# AAA_source-all_on_top.net
KiCad netlist of a schematic drawn in EAGLE
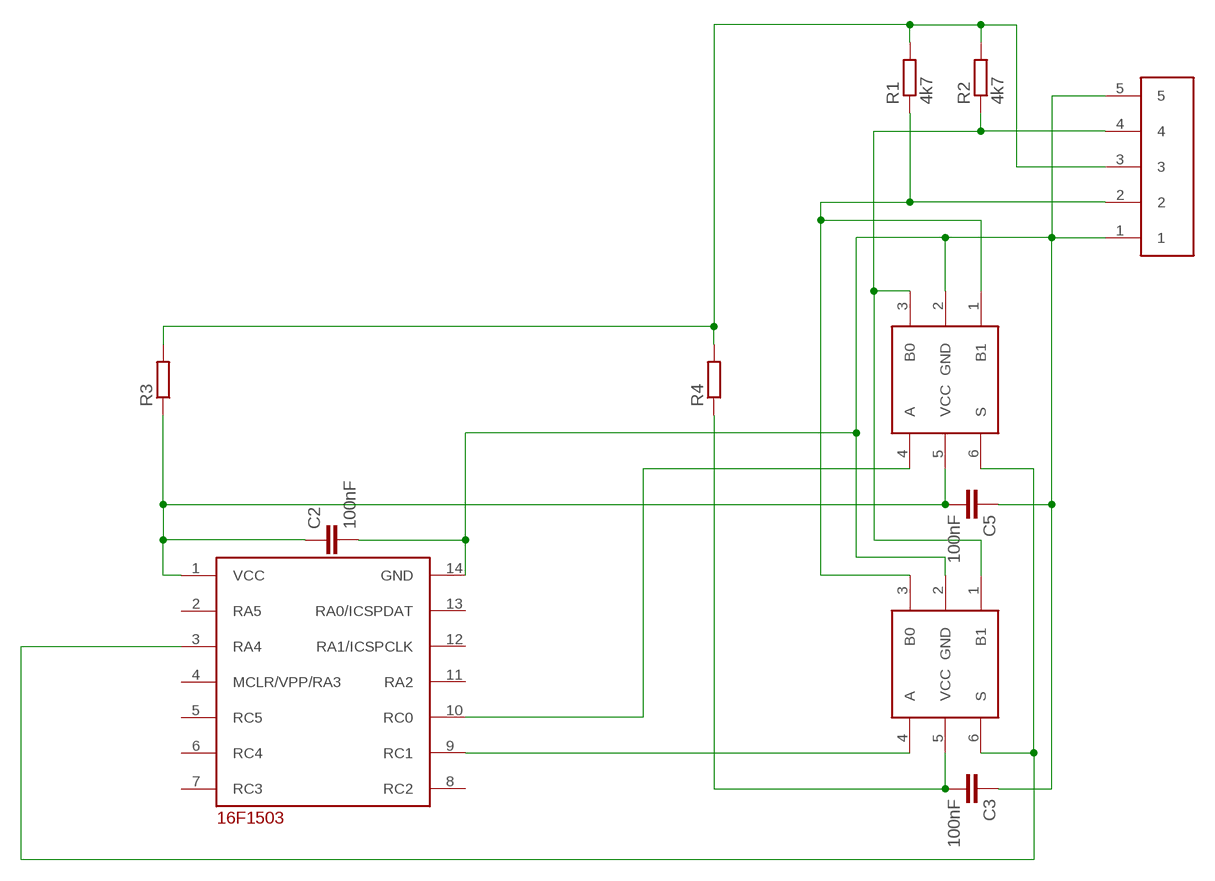
[diagram p0: schematic, sheet 1]

(export (version "E")
  (design (tool "Eeschema 10.0.6"))
  (components
    (comp (ref "C2")
      (value "100nF")
      (footprint "eagle-import:C0603")
      (libsource (lib "eagle-import") (part "C-EUC0603"))
    )
    (comp (ref "C3")
      (value "100nF")
      (footprint "eagle-import:C0603")
      (libsource (lib "eagle-import") (part "C-EUC0603"))
    )
    (comp (ref "C5")
      (value "100nF")
      (footprint "eagle-import:C0603")
      (libsource (lib "eagle-import") (part "C-EUC0603"))
    )
    (comp (ref "R1")
      (value "4k7")
      (footprint "eagle-import:R0603")
      (libsource (lib "eagle-import") (part "R-EU_R0603"))
    )
    (comp (ref "R2")
      (value "4k7")
      (footprint "eagle-import:R0603")
      (libsource (lib "eagle-import") (part "R-EU_R0603"))
    )
    (comp (ref "R3")
      (value "R-EU_R1206")
      (footprint "eagle-import:R1206")
      (libsource (lib "eagle-import") (part "R-EU_R1206"))
    )
    (comp (ref "R4")
      (value "R-EU_R1206")
      (footprint "eagle-import:R1206")
      (libsource (lib "eagle-import") (part "R-EU_R1206"))
    )
    (comp (ref "U$1")
      (value "16F103-TSSOP")
      (footprint "eagle-import:TSSOP14")
      (libsource (lib "eagle-import") (part "16F103-TSSOP"))
    )
    (comp (ref "U$5")
      (value "JUMPER5F-90")
      (footprint "eagle-import:JUMPER5F-90")
      (libsource (lib "eagle-import") (part "JUMPER5F-90"))
    )
    (comp (ref "U$6")
      (value "NC7SB3157P6X")
      (footprint "eagle-import:SC70-6L")
      (libsource (lib "eagle-import") (part "NC7SB3157P6X"))
    )
    (comp (ref "U$7")
      (value "NC7SB3157P6X")
      (footprint "eagle-import:SC70-6L")
      (libsource (lib "eagle-import") (part "NC7SB3157P6X"))
    )
  )
  (nets
    (net (code "1") (name "Net-(R1-Pad2)") (class "Default")
      (node (ref "R1") (pin "2") (pinfunction "2_2") (pintype "passive"))
      (node (ref "R2") (pin "2") (pinfunction "2_2") (pintype "passive"))
      (node (ref "R3") (pin "2") (pinfunction "2_2") (pintype "passive"))
      (node (ref "R4") (pin "2") (pinfunction "2_2") (pintype "passive"))
      (node (ref "U$5") (pin "3") (pinfunction "3_3") (pintype "bidirectional"))
    )
    (net (code "2") (name "Net-(U$1-GND)") (class "Default")
      (node (ref "C2") (pin "2") (pinfunction "2_2") (pintype "passive"))
      (node (ref "C3") (pin "1") (pinfunction "1_1") (pintype "passive"))
      (node (ref "C5") (pin "1") (pinfunction "1_1") (pintype "passive"))
      (node (ref "U$1") (pin "14") (pinfunction "GND_14") (pintype "power_in"))
      (node (ref "U$5") (pin "1") (pinfunction "1_1") (pintype "bidirectional"))
      (node (ref "U$5") (pin "5") (pinfunction "5_5") (pintype "bidirectional"))
      (node (ref "U$6") (pin "2") (pinfunction "GND_2") (pintype "power_in"))
      (node (ref "U$7") (pin "2") (pinfunction "GND_2") (pintype "power_in"))
    )
    (net (code "3") (name "Net-(U$1-RA4)") (class "Default")
      (node (ref "U$1") (pin "3") (pinfunction "RA4_3") (pintype "bidirectional"))
      (node (ref "U$6") (pin "6") (pinfunction "S_6") (pintype "bidirectional"))
      (node (ref "U$7") (pin "6") (pinfunction "S_6") (pintype "bidirectional"))
    )
    (net (code "4") (name "Net-(U$1-RC0)") (class "Default")
      (node (ref "U$1") (pin "10") (pinfunction "RC0_10") (pintype "bidirectional"))
      (node (ref "U$6") (pin "4") (pinfunction "A_4") (pintype "bidirectional"))
    )
    (net (code "5") (name "Net-(U$1-RC1)") (class "Default")
      (node (ref "U$1") (pin "9") (pinfunction "RC1_9") (pintype "bidirectional"))
      (node (ref "U$7") (pin "4") (pinfunction "A_4") (pintype "bidirectional"))
    )
    (net (code "6") (name "Net-(U$1-VCC)") (class "Default")
      (node (ref "C2") (pin "1") (pinfunction "1_1") (pintype "passive"))
      (node (ref "C5") (pin "2") (pinfunction "2_2") (pintype "passive"))
      (node (ref "R3") (pin "1") (pinfunction "1_1") (pintype "passive"))
      (node (ref "U$1") (pin "1") (pinfunction "VCC_1") (pintype "power_in"))
      (node (ref "U$6") (pin "5") (pinfunction "VCC_5") (pintype "power_in"))
    )
    (net (code "7") (name "Net-(U$6-B0)") (class "Default")
      (node (ref "R2") (pin "1") (pinfunction "1_1") (pintype "passive"))
      (node (ref "U$5") (pin "4") (pinfunction "4_4") (pintype "bidirectional"))
      (node (ref "U$6") (pin "3") (pinfunction "B0_3") (pintype "bidirectional"))
      (node (ref "U$7") (pin "1") (pinfunction "B1_1") (pintype "bidirectional"))
    )
    (net (code "8") (name "Net-(U$6-B1)") (class "Default")
      (node (ref "R1") (pin "1") (pinfunction "1_1") (pintype "passive"))
      (node (ref "U$5") (pin "2") (pinfunction "2_2") (pintype "bidirectional"))
      (node (ref "U$6") (pin "1") (pinfunction "B1_1") (pintype "bidirectional"))
      (node (ref "U$7") (pin "3") (pinfunction "B0_3") (pintype "bidirectional"))
    )
    (net (code "9") (name "Net-(U$7-VCC)") (class "Default")
      (node (ref "C3") (pin "2") (pinfunction "2_2") (pintype "passive"))
      (node (ref "R4") (pin "1") (pinfunction "1_1") (pintype "passive"))
      (node (ref "U$7") (pin "5") (pinfunction "VCC_5") (pintype "power_in"))
    )
    (net (code "10") (name "unconnected-(U$1-MCLR{slash}VPP{slash}RA3-Pad4)") (class "Default")
      (node (ref "U$1") (pin "4") (pinfunction "MCLR/VPP/RA3_4") (pintype "bidirectional"))
    )
    (net (code "11") (name "unconnected-(U$1-RA0{slash}ICSPDAT-Pad13)") (class "Default")
      (node (ref "U$1") (pin "13") (pinfunction "RA0/ICSPDAT_13") (pintype "bidirectional"))
    )
    (net (code "12") (name "unconnected-(U$1-RA1{slash}ICSPCLK-Pad12)") (class "Default")
      (node (ref "U$1") (pin "12") (pinfunction "RA1/ICSPCLK_12") (pintype "bidirectional"))
    )
    (net (code "13") (name "unconnected-(U$1-RA2-Pad11)") (class "Default")
      (node (ref "U$1") (pin "11") (pinfunction "RA2_11") (pintype "bidirectional"))
    )
    (net (code "14") (name "unconnected-(U$1-RA5-Pad2)") (class "Default")
      (node (ref "U$1") (pin "2") (pinfunction "RA5_2") (pintype "bidirectional"))
    )
    (net (code "15") (name "unconnected-(U$1-RC2-Pad8)") (class "Default")
      (node (ref "U$1") (pin "8") (pinfunction "RC2_8") (pintype "bidirectional"))
    )
    (net (code "16") (name "unconnected-(U$1-RC3-Pad7)") (class "Default")
      (node (ref "U$1") (pin "7") (pinfunction "RC3_7") (pintype "bidirectional"))
    )
    (net (code "17") (name "unconnected-(U$1-RC4-Pad6)") (class "Default")
      (node (ref "U$1") (pin "6") (pinfunction "RC4_6") (pintype "bidirectional"))
    )
    (net (code "18") (name "unconnected-(U$1-RC5-Pad5)") (class "Default")
      (node (ref "U$1") (pin "5") (pinfunction "RC5_5") (pintype "bidirectional"))
    )
  )
)
